# GOTOWAP_YTKA.net
KiCad netlist of a schematic drawn in EAGLE
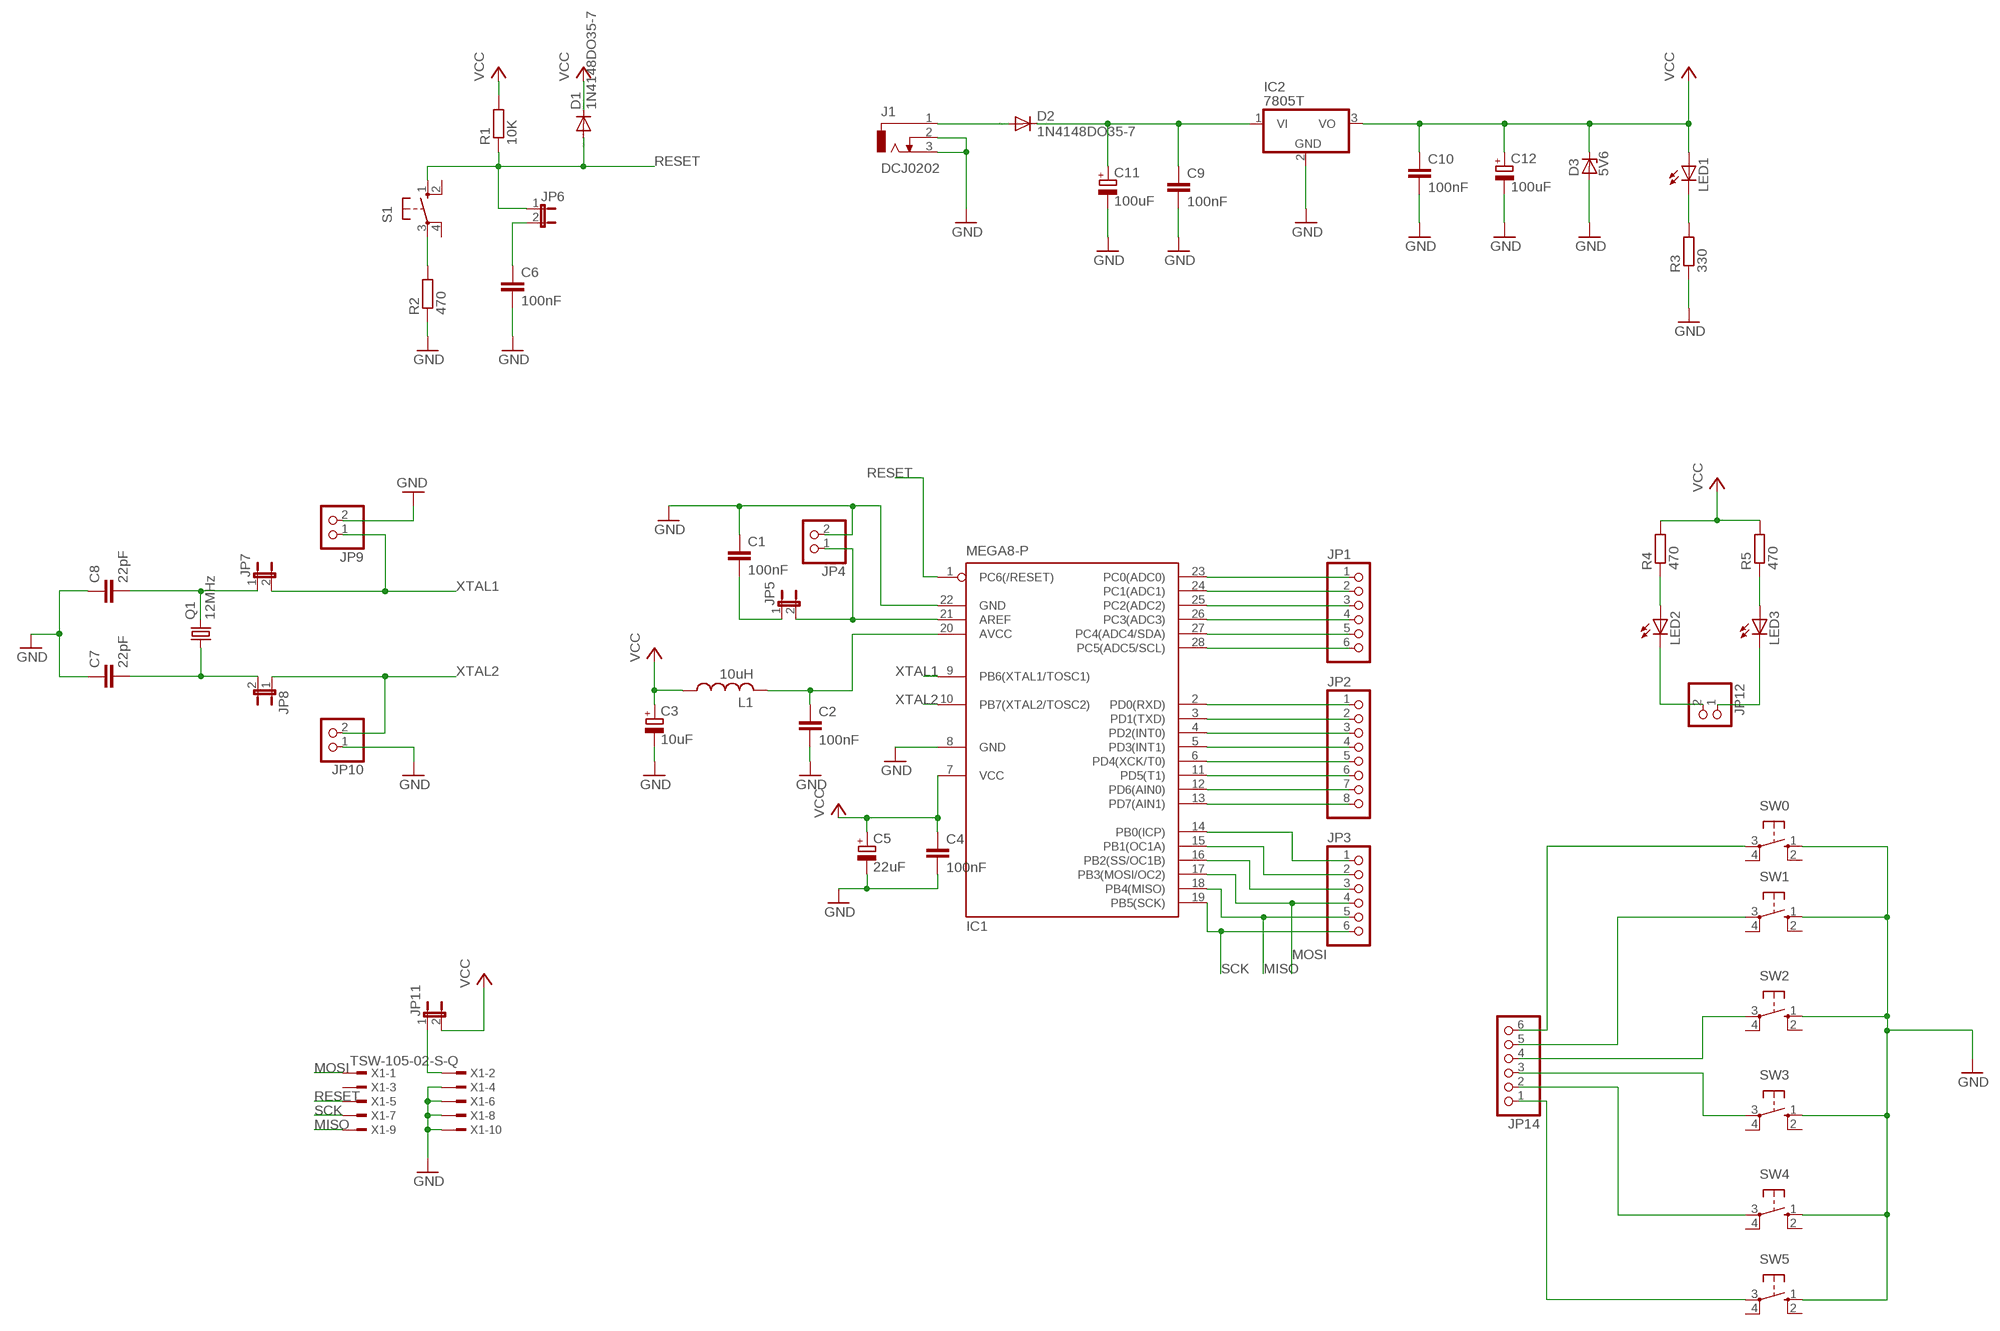
[diagram p0: schematic, sheet 1]

(export (version "E")
  (design (tool "Eeschema 10.0.6"))
  (components
    (comp (ref "C1")
      (value "100nF")
      (footprint "eagle-import:C025-025X050")
      (libsource (lib "eagle-import") (part "C-EU025-025X050"))
    )
    (comp (ref "C2")
      (value "100nF")
      (footprint "eagle-import:C025-025X050")
      (libsource (lib "eagle-import") (part "resistor_C-EU025-025X050"))
    )
    (comp (ref "C3")
      (value "10uF")
      (footprint "eagle-import:B45181B")
      (libsource (lib "eagle-import") (part "CPOL-EUB45181B"))
    )
    (comp (ref "C4")
      (value "100nF")
      (footprint "eagle-import:C025-025X050")
      (libsource (lib "eagle-import") (part "resistor_C-EU025-025X050"))
    )
    (comp (ref "C5")
      (value "22uF")
      (footprint "eagle-import:B45181B")
      (libsource (lib "eagle-import") (part "CPOL-EUB45181B"))
    )
    (comp (ref "C6")
      (value "100nF")
      (footprint "eagle-import:C025-025X050")
      (libsource (lib "eagle-import") (part "resistor_C-EU025-025X050"))
    )
    (comp (ref "C7")
      (value "22pF")
      (footprint "eagle-import:C025-025X050")
      (libsource (lib "eagle-import") (part "resistor_C-EU025-025X050"))
    )
    (comp (ref "C8")
      (value "22pF")
      (footprint "eagle-import:C025-025X050")
      (libsource (lib "eagle-import") (part "resistor_C-EU025-025X050"))
    )
    (comp (ref "C9")
      (value "100nF")
      (footprint "eagle-import:C025-025X050")
      (libsource (lib "eagle-import") (part "resistor_C-EU025-025X050"))
    )
    (comp (ref "C10")
      (value "100nF")
      (footprint "eagle-import:C025-025X050")
      (libsource (lib "eagle-import") (part "resistor_C-EU025-025X050"))
    )
    (comp (ref "C11")
      (value "100uF")
      (footprint "eagle-import:B45181B")
      (libsource (lib "eagle-import") (part "CPOL-EUB45181B"))
    )
    (comp (ref "C12")
      (value "100uF")
      (footprint "eagle-import:B45181B")
      (libsource (lib "eagle-import") (part "CPOL-EUB45181B"))
    )
    (comp (ref "D1")
      (value "1N4148DO35-7")
      (footprint "eagle-import:DO35-7")
      (libsource (lib "eagle-import") (part "1N4148DO35-7"))
    )
    (comp (ref "D2")
      (value "1N4148DO35-7")
      (footprint "eagle-import:DO35-7")
      (libsource (lib "eagle-import") (part "1N4148DO35-7"))
    )
    (comp (ref "D3")
      (value "5V6")
      (footprint "eagle-import:C1702-15")
      (libsource (lib "eagle-import") (part "ZENER-DIODEC1702-15"))
    )
    (comp (ref "IC1")
      (value "MEGA8-P")
      (footprint "eagle-import:DIL28-3")
      (libsource (lib "eagle-import") (part "MEGA8-P"))
    )
    (comp (ref "IC2")
      (value "7805T")
      (footprint "eagle-import:TO220H")
      (libsource (lib "eagle-import") (part "78T05"))
    )
    (comp (ref "J1")
      (value "DCJ0202")
      (footprint "eagle-import:DCJ0202")
      (libsource (lib "eagle-import") (part "DCJ0202"))
    )
    (comp (ref "JP1")
      (value "PINHD-1X6")
      (footprint "eagle-import:1X06")
      (libsource (lib "eagle-import") (part "PINHD-1X6"))
    )
    (comp (ref "JP2")
      (value "PINHD-1X8")
      (footprint "eagle-import:1X08")
      (libsource (lib "eagle-import") (part "PINHD-1X8"))
    )
    (comp (ref "JP3")
      (value "PINHD-1X6")
      (footprint "eagle-import:1X06")
      (libsource (lib "eagle-import") (part "PINHD-1X6"))
    )
    (comp (ref "JP4")
      (value "PINHD-1X2")
      (footprint "eagle-import:1X02")
      (libsource (lib "eagle-import") (part "PINHD-1X2"))
    )
    (comp (ref "JP5")
      (value "JP1E")
      (footprint "eagle-import:JP1")
      (libsource (lib "eagle-import") (part "JP1E"))
    )
    (comp (ref "JP6")
      (value "JP1E")
      (footprint "eagle-import:JP1")
      (libsource (lib "eagle-import") (part "JP1E"))
    )
    (comp (ref "JP7")
      (value "JP1E")
      (footprint "eagle-import:JP1")
      (libsource (lib "eagle-import") (part "JP1E"))
    )
    (comp (ref "JP8")
      (value "JP1E")
      (footprint "eagle-import:JP1")
      (libsource (lib "eagle-import") (part "JP1E"))
    )
    (comp (ref "JP9")
      (value "PINHD-1X2")
      (footprint "eagle-import:1X02")
      (libsource (lib "eagle-import") (part "PINHD-1X2"))
    )
    (comp (ref "JP10")
      (value "PINHD-1X2")
      (footprint "eagle-import:1X02")
      (libsource (lib "eagle-import") (part "PINHD-1X2"))
    )
    (comp (ref "JP11")
      (value "JP1E")
      (footprint "eagle-import:JP1")
      (libsource (lib "eagle-import") (part "JP1E"))
    )
    (comp (ref "JP12")
      (value "PINHD-1X2")
      (footprint "eagle-import:1X02")
      (libsource (lib "eagle-import") (part "PINHD-1X2"))
    )
    (comp (ref "JP14")
      (value "PINHD-1X6")
      (footprint "eagle-import:1X06")
      (libsource (lib "eagle-import") (part "PINHD-1X6"))
    )
    (comp (ref "L1")
      (value "10uH")
      (footprint "eagle-import:0204_7")
      (libsource (lib "eagle-import") (part "L-US0204/7"))
    )
    (comp (ref "LED1")
      (value "LED5MM")
      (footprint "eagle-import:LED5MM")
      (libsource (lib "eagle-import") (part "LED5MM"))
    )
    (comp (ref "LED2")
      (value "LED5MM")
      (footprint "eagle-import:LED5MM")
      (libsource (lib "eagle-import") (part "LED5MM"))
    )
    (comp (ref "LED3")
      (value "LED5MM")
      (footprint "eagle-import:LED5MM")
      (libsource (lib "eagle-import") (part "LED5MM"))
    )
    (comp (ref "Q1")
      (value "12MHz")
      (footprint "eagle-import:HC49U-V")
      (libsource (lib "eagle-import") (part "CRYSTALHC49U-V"))
    )
    (comp (ref "R1")
      (value "10K")
      (footprint "eagle-import:0204_7")
      (libsource (lib "eagle-import") (part "R-EU_0204/7"))
    )
    (comp (ref "R2")
      (value "470")
      (footprint "eagle-import:0204_7")
      (libsource (lib "eagle-import") (part "R-EU_0204/7"))
    )
    (comp (ref "R3")
      (value "330")
      (footprint "eagle-import:0204_7")
      (libsource (lib "eagle-import") (part "R-EU_0204/7"))
    )
    (comp (ref "R4")
      (value "470")
      (footprint "eagle-import:0204_7")
      (libsource (lib "eagle-import") (part "R-EU_0204/7"))
    )
    (comp (ref "R5")
      (value "470")
      (footprint "eagle-import:0204_7")
      (libsource (lib "eagle-import") (part "R-EU_0204/7"))
    )
    (comp (ref "S1")
      (value "10-XX")
      (footprint "eagle-import:B3F-10XX")
      (fields (field (name "MPN") "B3F-1000"))
      (libsource (lib "eagle-import") (part "10-XX"))
    )
    (comp (ref "SW0")
      (value "10-XX")
      (footprint "eagle-import:B3F-10XX")
      (fields (field (name "MPN") "B3F-1000"))
      (libsource (lib "eagle-import") (part "10-XX"))
    )
    (comp (ref "SW1")
      (value "10-XX")
      (footprint "eagle-import:B3F-10XX")
      (fields (field (name "MPN") "B3F-1000"))
      (libsource (lib "eagle-import") (part "10-XX"))
    )
    (comp (ref "SW2")
      (value "10-XX")
      (footprint "eagle-import:B3F-10XX")
      (fields (field (name "MPN") "B3F-1000"))
      (libsource (lib "eagle-import") (part "10-XX"))
    )
    (comp (ref "SW3")
      (value "10-XX")
      (footprint "eagle-import:B3F-10XX")
      (fields (field (name "MPN") "B3F-1000"))
      (libsource (lib "eagle-import") (part "10-XX"))
    )
    (comp (ref "SW4")
      (value "10-XX")
      (footprint "eagle-import:B3F-10XX")
      (fields (field (name "MPN") "B3F-1000"))
      (libsource (lib "eagle-import") (part "10-XX"))
    )
    (comp (ref "SW5")
      (value "10-XX")
      (footprint "eagle-import:B3F-10XX")
      (fields (field (name "MPN") "B3F-1000"))
      (libsource (lib "eagle-import") (part "10-XX"))
    )
    (comp (ref "X1")
      (value "TSW-105-02-S-Q")
      (footprint "eagle-import:TSW-105-02-S-Q")
      (libsource (lib "eagle-import") (part "TSW-105-02-S-Q"))
    )
  )
  (nets
    (net (code "1") (name "/MISO") (class "Default")
      (node (ref "IC1") (pin "18") (pinfunction "PB4(MISO)_18") (pintype "bidirectional"))
      (node (ref "JP3") (pin "5") (pinfunction "5_5") (pintype "passive"))
      (node (ref "X1") (pin "9") (pinfunction "1_9") (pintype "passive"))
    )
    (net (code "2") (name "/MOSI") (class "Default")
      (node (ref "IC1") (pin "17") (pinfunction "PB3(MOSI/OC2)_17") (pintype "bidirectional"))
      (node (ref "JP3") (pin "4") (pinfunction "4_4") (pintype "passive"))
      (node (ref "X1") (pin "1") (pinfunction "1_1") (pintype "passive"))
    )
    (net (code "3") (name "/RESET") (class "Default")
      (node (ref "D1") (pin "A") (pinfunction "A_A") (pintype "passive"))
      (node (ref "IC1") (pin "1") (pinfunction "PC6(/RESET)_1") (pintype "bidirectional"))
      (node (ref "JP6") (pin "1") (pinfunction "1_1") (pintype "passive"))
      (node (ref "R1") (pin "1") (pinfunction "1_1") (pintype "passive"))
      (node (ref "S1") (pin "1") (pinfunction "S_1") (pintype "passive"))
      (node (ref "X1") (pin "5") (pinfunction "1_5") (pintype "passive"))
    )
    (net (code "4") (name "/SCK") (class "Default")
      (node (ref "IC1") (pin "19") (pinfunction "PB5(SCK)_19") (pintype "bidirectional"))
      (node (ref "JP3") (pin "6") (pinfunction "6_6") (pintype "passive"))
      (node (ref "X1") (pin "7") (pinfunction "1_7") (pintype "passive"))
    )
    (net (code "5") (name "/XTAL1") (class "Default")
      (node (ref "IC1") (pin "9") (pinfunction "PB6(XTAL1/TOSC1)_9") (pintype "bidirectional"))
      (node (ref "JP7") (pin "2") (pinfunction "2_2") (pintype "passive"))
      (node (ref "JP9") (pin "1") (pinfunction "1_1") (pintype "passive"))
    )
    (net (code "6") (name "/XTAL2") (class "Default")
      (node (ref "IC1") (pin "10") (pinfunction "PB7(XTAL2/TOSC2)_10") (pintype "bidirectional"))
      (node (ref "JP10") (pin "2") (pinfunction "2_2") (pintype "passive"))
      (node (ref "JP8") (pin "1") (pinfunction "1_1") (pintype "passive"))
    )
    (net (code "7") (name "GND") (class "Default")
      (node (ref "C1") (pin "1") (pinfunction "1_1") (pintype "passive"))
      (node (ref "C10") (pin "2") (pinfunction "2_2") (pintype "passive"))
      (node (ref "C11") (pin "-") (pinfunction "-_-") (pintype "passive"))
      (node (ref "C12") (pin "-") (pinfunction "-_-") (pintype "passive"))
      (node (ref "C2") (pin "2") (pinfunction "2_2") (pintype "passive"))
      (node (ref "C3") (pin "-") (pinfunction "-_-") (pintype "passive"))
      (node (ref "C4") (pin "2") (pinfunction "2_2") (pintype "passive"))
      (node (ref "C5") (pin "-") (pinfunction "-_-") (pintype "passive"))
      (node (ref "C6") (pin "2") (pinfunction "2_2") (pintype "passive"))
      (node (ref "C7") (pin "1") (pinfunction "1_1") (pintype "passive"))
      (node (ref "C8") (pin "1") (pinfunction "1_1") (pintype "passive"))
      (node (ref "C9") (pin "2") (pinfunction "2_2") (pintype "passive"))
      (node (ref "D3") (pin "A") (pinfunction "A_A") (pintype "passive"))
      (node (ref "IC1") (pin "22") (pinfunction "GND_22") (pintype "power_in"))
      (node (ref "IC1") (pin "8") (pinfunction "GND_8") (pintype "power_in"))
      (node (ref "IC2") (pin "2") (pinfunction "GND_2") (pintype "passive"))
      (node (ref "J1") (pin "2") (pinfunction "2_2") (pintype "passive"))
      (node (ref "J1") (pin "3") (pinfunction "3_3") (pintype "passive"))
      (node (ref "JP10") (pin "1") (pinfunction "1_1") (pintype "passive"))
      (node (ref "JP4") (pin "2") (pinfunction "2_2") (pintype "passive"))
      (node (ref "JP9") (pin "2") (pinfunction "2_2") (pintype "passive"))
      (node (ref "R2") (pin "1") (pinfunction "1_1") (pintype "passive"))
      (node (ref "R3") (pin "1") (pinfunction "1_1") (pintype "passive"))
      (node (ref "SW0") (pin "1") (pinfunction "S_1") (pintype "passive"))
      (node (ref "SW1") (pin "1") (pinfunction "S_1") (pintype "passive"))
      (node (ref "SW2") (pin "1") (pinfunction "S_1") (pintype "passive"))
      (node (ref "SW3") (pin "1") (pinfunction "S_1") (pintype "passive"))
      (node (ref "SW4") (pin "1") (pinfunction "S_1") (pintype "passive"))
      (node (ref "SW5") (pin "1") (pinfunction "S_1") (pintype "passive"))
      (node (ref "X1") (pin "10") (pinfunction "1_10") (pintype "passive"))
      (node (ref "X1") (pin "4") (pinfunction "1_4") (pintype "passive"))
      (node (ref "X1") (pin "6") (pinfunction "1_6") (pintype "passive"))
      (node (ref "X1") (pin "8") (pinfunction "1_8") (pintype "passive"))
    )
    (net (code "8") (name "Net-(C1-Pad2)") (class "Default")
      (node (ref "C1") (pin "2") (pinfunction "2_2") (pintype "passive"))
      (node (ref "JP5") (pin "1") (pinfunction "1_1") (pintype "passive"))
    )
    (net (code "9") (name "Net-(C6-Pad1)") (class "Default")
      (node (ref "C6") (pin "1") (pinfunction "1_1") (pintype "passive"))
      (node (ref "JP6") (pin "2") (pinfunction "2_2") (pintype "passive"))
    )
    (net (code "10") (name "Net-(C7-Pad2)") (class "Default")
      (node (ref "C7") (pin "2") (pinfunction "2_2") (pintype "passive"))
      (node (ref "JP8") (pin "2") (pinfunction "2_2") (pintype "passive"))
      (node (ref "Q1") (pin "1") (pinfunction "1_1") (pintype "passive"))
    )
    (net (code "11") (name "Net-(C8-Pad2)") (class "Default")
      (node (ref "C8") (pin "2") (pinfunction "2_2") (pintype "passive"))
      (node (ref "JP7") (pin "1") (pinfunction "1_1") (pintype "passive"))
      (node (ref "Q1") (pin "2") (pinfunction "2_2") (pintype "passive"))
    )
    (net (code "12") (name "Net-(D2-PadA)") (class "Default")
      (node (ref "D2") (pin "A") (pinfunction "A_A") (pintype "passive"))
      (node (ref "J1") (pin "1") (pinfunction "1_1") (pintype "passive"))
    )
    (net (code "13") (name "Net-(IC1-AREF)") (class "Default")
      (node (ref "IC1") (pin "21") (pinfunction "AREF_21") (pintype "passive"))
      (node (ref "JP4") (pin "1") (pinfunction "1_1") (pintype "passive"))
      (node (ref "JP5") (pin "2") (pinfunction "2_2") (pintype "passive"))
    )
    (net (code "14") (name "Net-(IC1-AVCC)") (class "Default")
      (node (ref "C2") (pin "1") (pinfunction "1_1") (pintype "passive"))
      (node (ref "IC1") (pin "20") (pinfunction "AVCC_20") (pintype "power_in"))
      (node (ref "L1") (pin "2") (pinfunction "2_2") (pintype "passive"))
    )
    (net (code "15") (name "Net-(IC1-PB0(ICP))") (class "Default")
      (node (ref "IC1") (pin "14") (pinfunction "PB0(ICP)_14") (pintype "bidirectional"))
      (node (ref "JP3") (pin "1") (pinfunction "1_1") (pintype "passive"))
    )
    (net (code "16") (name "Net-(IC1-PB1(OC1A))") (class "Default")
      (node (ref "IC1") (pin "15") (pinfunction "PB1(OC1A)_15") (pintype "bidirectional"))
      (node (ref "JP3") (pin "2") (pinfunction "2_2") (pintype "passive"))
    )
    (net (code "17") (name "Net-(IC1-PB2(SS{slash}OC1B))") (class "Default")
      (node (ref "IC1") (pin "16") (pinfunction "PB2(SS/OC1B)_16") (pintype "bidirectional"))
      (node (ref "JP3") (pin "3") (pinfunction "3_3") (pintype "passive"))
    )
    (net (code "18") (name "Net-(IC1-PC0(ADC0))") (class "Default")
      (node (ref "IC1") (pin "23") (pinfunction "PC0(ADC0)_23") (pintype "bidirectional"))
      (node (ref "JP1") (pin "1") (pinfunction "1_1") (pintype "passive"))
    )
    (net (code "19") (name "Net-(IC1-PC1(ADC1))") (class "Default")
      (node (ref "IC1") (pin "24") (pinfunction "PC1(ADC1)_24") (pintype "bidirectional"))
      (node (ref "JP1") (pin "2") (pinfunction "2_2") (pintype "passive"))
    )
    (net (code "20") (name "Net-(IC1-PC2(ADC2))") (class "Default")
      (node (ref "IC1") (pin "25") (pinfunction "PC2(ADC2)_25") (pintype "bidirectional"))
      (node (ref "JP1") (pin "3") (pinfunction "3_3") (pintype "passive"))
    )
    (net (code "21") (name "Net-(IC1-PC3(ADC3))") (class "Default")
      (node (ref "IC1") (pin "26") (pinfunction "PC3(ADC3)_26") (pintype "bidirectional"))
      (node (ref "JP1") (pin "4") (pinfunction "4_4") (pintype "passive"))
    )
    (net (code "22") (name "Net-(IC1-PC4(ADC4{slash}SDA))") (class "Default")
      (node (ref "IC1") (pin "27") (pinfunction "PC4(ADC4/SDA)_27") (pintype "bidirectional"))
      (node (ref "JP1") (pin "5") (pinfunction "5_5") (pintype "passive"))
    )
    (net (code "23") (name "Net-(IC1-PC5(ADC5{slash}SCL))") (class "Default")
      (node (ref "IC1") (pin "28") (pinfunction "PC5(ADC5/SCL)_28") (pintype "bidirectional"))
      (node (ref "JP1") (pin "6") (pinfunction "6_6") (pintype "passive"))
    )
    (net (code "24") (name "Net-(IC1-PD0(RXD))") (class "Default")
      (node (ref "IC1") (pin "2") (pinfunction "PD0(RXD)_2") (pintype "bidirectional"))
      (node (ref "JP2") (pin "1") (pinfunction "1_1") (pintype "passive"))
    )
    (net (code "25") (name "Net-(IC1-PD1(TXD))") (class "Default")
      (node (ref "IC1") (pin "3") (pinfunction "PD1(TXD)_3") (pintype "bidirectional"))
      (node (ref "JP2") (pin "2") (pinfunction "2_2") (pintype "passive"))
    )
    (net (code "26") (name "Net-(IC1-PD2(INT0))") (class "Default")
      (node (ref "IC1") (pin "4") (pinfunction "PD2(INT0)_4") (pintype "bidirectional"))
      (node (ref "JP2") (pin "3") (pinfunction "3_3") (pintype "passive"))
    )
    (net (code "27") (name "Net-(IC1-PD3(INT1))") (class "Default")
      (node (ref "IC1") (pin "5") (pinfunction "PD3(INT1)_5") (pintype "bidirectional"))
      (node (ref "JP2") (pin "4") (pinfunction "4_4") (pintype "passive"))
    )
    (net (code "28") (name "Net-(IC1-PD4(XCK{slash}T0))") (class "Default")
      (node (ref "IC1") (pin "6") (pinfunction "PD4(XCK/T0)_6") (pintype "bidirectional"))
      (node (ref "JP2") (pin "5") (pinfunction "5_5") (pintype "passive"))
    )
    (net (code "29") (name "Net-(IC1-PD5(T1))") (class "Default")
      (node (ref "IC1") (pin "11") (pinfunction "PD5(T1)_11") (pintype "bidirectional"))
      (node (ref "JP2") (pin "6") (pinfunction "6_6") (pintype "passive"))
    )
    (net (code "30") (name "Net-(IC1-PD6(AIN0))") (class "Default")
      (node (ref "IC1") (pin "12") (pinfunction "PD6(AIN0)_12") (pintype "bidirectional"))
      (node (ref "JP2") (pin "7") (pinfunction "7_7") (pintype "passive"))
    )
    (net (code "31") (name "Net-(IC1-PD7(AIN1))") (class "Default")
      (node (ref "IC1") (pin "13") (pinfunction "PD7(AIN1)_13") (pintype "bidirectional"))
      (node (ref "JP2") (pin "8") (pinfunction "8_8") (pintype "passive"))
    )
    (net (code "32") (name "Net-(IC2-VI)") (class "Default")
      (node (ref "C11") (pin "+") (pinfunction "+_+") (pintype "passive"))
      (node (ref "C9") (pin "1") (pinfunction "1_1") (pintype "passive"))
      (node (ref "D2") (pin "C") (pinfunction "C_C") (pintype "passive"))
      (node (ref "IC2") (pin "1") (pinfunction "VI_1") (pintype "input"))
    )
    (net (code "33") (name "Net-(LED1-C)") (class "Default")
      (node (ref "LED1") (pin "K") (pinfunction "C_K") (pintype "passive"))
      (node (ref "R3") (pin "2") (pinfunction "2_2") (pintype "passive"))
    )
    (net (code "34") (name "Net-(LED2-C)") (class "Default")
      (node (ref "JP12") (pin "2") (pinfunction "2_2") (pintype "passive"))
      (node (ref "LED2") (pin "K") (pinfunction "C_K") (pintype "passive"))
    )
    (net (code "35") (name "Net-(LED2-PadA)") (class "Default")
      (node (ref "LED2") (pin "A") (pinfunction "A_A") (pintype "passive"))
      (node (ref "R4") (pin "1") (pinfunction "1_1") (pintype "passive"))
    )
    (net (code "36") (name "Net-(LED3-C)") (class "Default")
      (node (ref "JP12") (pin "1") (pinfunction "1_1") (pintype "passive"))
      (node (ref "LED3") (pin "K") (pinfunction "C_K") (pintype "passive"))
    )
    (net (code "37") (name "Net-(LED3-PadA)") (class "Default")
      (node (ref "LED3") (pin "A") (pinfunction "A_A") (pintype "passive"))
      (node (ref "R5") (pin "1") (pinfunction "1_1") (pintype "passive"))
    )
    (net (code "38") (name "Net-(S1-P)") (class "Default")
      (node (ref "R2") (pin "2") (pinfunction "2_2") (pintype "passive"))
      (node (ref "S1") (pin "3") (pinfunction "P_3") (pintype "passive"))
    )
    (net (code "39") (name "Net-(SW0-P)") (class "Default")
      (node (ref "JP14") (pin "6") (pinfunction "6_6") (pintype "passive"))
      (node (ref "SW0") (pin "3") (pinfunction "P_3") (pintype "passive"))
    )
    (net (code "40") (name "Net-(SW1-P)") (class "Default")
      (node (ref "JP14") (pin "5") (pinfunction "5_5") (pintype "passive"))
      (node (ref "SW1") (pin "3") (pinfunction "P_3") (pintype "passive"))
    )
    (net (code "41") (name "Net-(SW2-P)") (class "Default")
      (node (ref "JP14") (pin "4") (pinfunction "4_4") (pintype "passive"))
      (node (ref "SW2") (pin "3") (pinfunction "P_3") (pintype "passive"))
    )
    (net (code "42") (name "Net-(SW3-P)") (class "Default")
      (node (ref "JP14") (pin "3") (pinfunction "3_3") (pintype "passive"))
      (node (ref "SW3") (pin "3") (pinfunction "P_3") (pintype "passive"))
    )
    (net (code "43") (name "Net-(SW4-P)") (class "Default")
      (node (ref "JP14") (pin "2") (pinfunction "2_2") (pintype "passive"))
      (node (ref "SW4") (pin "3") (pinfunction "P_3") (pintype "passive"))
    )
    (net (code "44") (name "Net-(SW5-P)") (class "Default")
      (node (ref "JP14") (pin "1") (pinfunction "1_1") (pintype "passive"))
      (node (ref "SW5") (pin "3") (pinfunction "P_3") (pintype "passive"))
    )
    (net (code "45") (name "Net-(X1C-1)") (class "Default")
      (node (ref "JP11") (pin "1") (pinfunction "1_1") (pintype "passive"))
      (node (ref "X1") (pin "2") (pinfunction "1_2") (pintype "passive"))
    )
    (net (code "46") (name "VCC") (class "Default")
      (node (ref "C10") (pin "1") (pinfunction "1_1") (pintype "passive"))
      (node (ref "C12") (pin "+") (pinfunction "+_+") (pintype "passive"))
      (node (ref "C3") (pin "+") (pinfunction "+_+") (pintype "passive"))
      (node (ref "C4") (pin "1") (pinfunction "1_1") (pintype "passive"))
      (node (ref "C5") (pin "+") (pinfunction "+_+") (pintype "passive"))
      (node (ref "D1") (pin "C") (pinfunction "C_C") (pintype "passive"))
      (node (ref "D3") (pin "C") (pinfunction "C_C") (pintype "passive"))
      (node (ref "IC1") (pin "7") (pinfunction "VCC_7") (pintype "power_in"))
      (node (ref "IC2") (pin "3") (pinfunction "VO_3") (pintype "passive"))
      (node (ref "JP11") (pin "2") (pinfunction "2_2") (pintype "passive"))
      (node (ref "L1") (pin "1") (pinfunction "1_1") (pintype "passive"))
      (node (ref "LED1") (pin "A") (pinfunction "A_A") (pintype "passive"))
      (node (ref "R1") (pin "2") (pinfunction "2_2") (pintype "passive"))
      (node (ref "R4") (pin "2") (pinfunction "2_2") (pintype "passive"))
      (node (ref "R5") (pin "2") (pinfunction "2_2") (pintype "passive"))
    )
    (net (code "47") (name "unconnected-(S1-P1-Pad4)") (class "Default")
      (node (ref "S1") (pin "4") (pinfunction "P1_4") (pintype "passive"))
    )
    (net (code "48") (name "unconnected-(S1-S1-Pad2)") (class "Default")
      (node (ref "S1") (pin "2") (pinfunction "S1_2") (pintype "passive"))
    )
    (net (code "49") (name "unconnected-(SW0-P1-Pad4)") (class "Default")
      (node (ref "SW0") (pin "4") (pinfunction "P1_4") (pintype "passive"))
    )
    (net (code "50") (name "unconnected-(SW0-S1-Pad2)") (class "Default")
      (node (ref "SW0") (pin "2") (pinfunction "S1_2") (pintype "passive"))
    )
    (net (code "51") (name "unconnected-(SW1-P1-Pad4)") (class "Default")
      (node (ref "SW1") (pin "4") (pinfunction "P1_4") (pintype "passive"))
    )
    (net (code "52") (name "unconnected-(SW1-S1-Pad2)") (class "Default")
      (node (ref "SW1") (pin "2") (pinfunction "S1_2") (pintype "passive"))
    )
    (net (code "53") (name "unconnected-(SW2-P1-Pad4)") (class "Default")
      (node (ref "SW2") (pin "4") (pinfunction "P1_4") (pintype "passive"))
    )
    (net (code "54") (name "unconnected-(SW2-S1-Pad2)") (class "Default")
      (node (ref "SW2") (pin "2") (pinfunction "S1_2") (pintype "passive"))
    )
    (net (code "55") (name "unconnected-(SW3-P1-Pad4)") (class "Default")
      (node (ref "SW3") (pin "4") (pinfunction "P1_4") (pintype "passive"))
    )
    (net (code "56") (name "unconnected-(SW3-S1-Pad2)") (class "Default")
      (node (ref "SW3") (pin "2") (pinfunction "S1_2") (pintype "passive"))
    )
    (net (code "57") (name "unconnected-(SW4-P1-Pad4)") (class "Default")
      (node (ref "SW4") (pin "4") (pinfunction "P1_4") (pintype "passive"))
    )
    (net (code "58") (name "unconnected-(SW4-S1-Pad2)") (class "Default")
      (node (ref "SW4") (pin "2") (pinfunction "S1_2") (pintype "passive"))
    )
    (net (code "59") (name "unconnected-(SW5-P1-Pad4)") (class "Default")
      (node (ref "SW5") (pin "4") (pinfunction "P1_4") (pintype "passive"))
    )
    (net (code "60") (name "unconnected-(SW5-S1-Pad2)") (class "Default")
      (node (ref "SW5") (pin "2") (pinfunction "S1_2") (pintype "passive"))
    )
    (net (code "61") (name "unconnected-(X1D-1-Pad3)") (class "Default")
      (node (ref "X1") (pin "3") (pinfunction "1_3") (pintype "passive"))
    )
  )
)
